# IOTBeev0_21.net
KiCad netlist of a schematic drawn in EAGLE
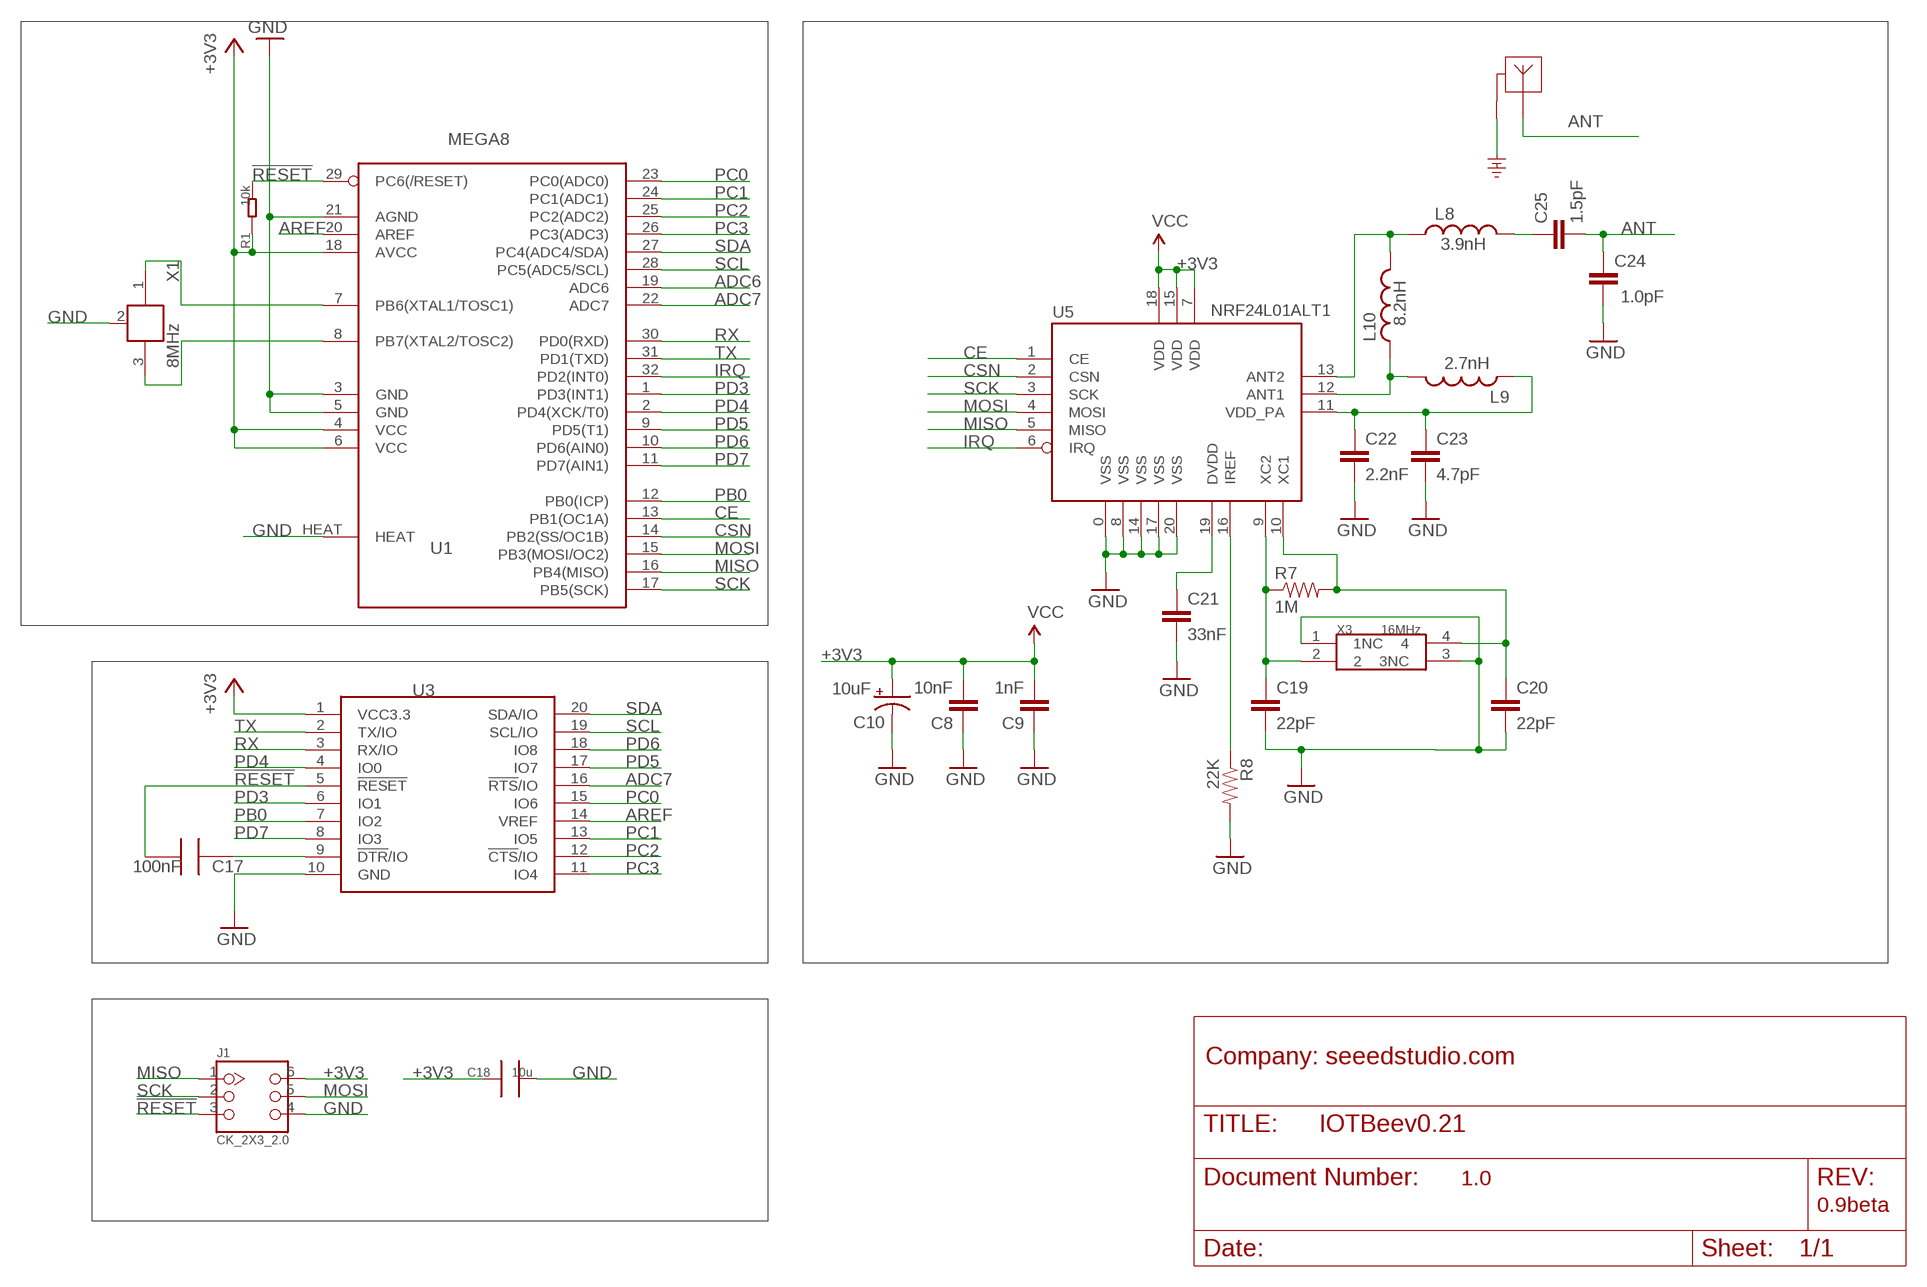
[diagram p0: schematic, sheet 1]

(export (version "E")
  (design (tool "Eeschema 10.0.6"))
  (components
    (comp (ref "ANT1")
      (value "2.4G-ANT")
      (footprint "eagle-import:2.4G-ANT")
      (libsource (lib "eagle-import") (part "2.4G-ANT"))
    )
    (comp (ref "C8")
      (value "10nF")
      (footprint "eagle-import:0402-CAP")
      (libsource (lib "eagle-import") (part "CAP0402-CAP"))
    )
    (comp (ref "C9")
      (value "1nF")
      (footprint "eagle-import:0402-CAP")
      (libsource (lib "eagle-import") (part "CAP0402-CAP"))
    )
    (comp (ref "C10")
      (value "10uF")
      (footprint "eagle-import:EIA3528")
      (libsource (lib "eagle-import") (part "CAP_POL3528"))
    )
    (comp (ref "C17")
      (value "100nF")
      (footprint "eagle-import:0603_S")
      (libsource (lib "eagle-import") (part "C0603_S"))
    )
    (comp (ref "C18")
      (value "10u")
      (footprint "eagle-import:0805")
      (libsource (lib "eagle-import") (part "C0805"))
    )
    (comp (ref "C19")
      (value "22pF")
      (footprint "eagle-import:0402-CAP")
      (libsource (lib "eagle-import") (part "CAP0402-CAP"))
    )
    (comp (ref "C20")
      (value "22pF")
      (footprint "eagle-import:0402-CAP")
      (libsource (lib "eagle-import") (part "CAP0402-CAP"))
    )
    (comp (ref "C21")
      (value "33nF")
      (footprint "eagle-import:0402-CAP")
      (libsource (lib "eagle-import") (part "CAP0402-CAP"))
    )
    (comp (ref "C22")
      (value "2.2nF")
      (footprint "eagle-import:0402-CAP")
      (libsource (lib "eagle-import") (part "CAP0402-CAP"))
    )
    (comp (ref "C23")
      (value "4.7pF")
      (footprint "eagle-import:0402-CAP")
      (libsource (lib "eagle-import") (part "CAP0402-CAP"))
    )
    (comp (ref "C24")
      (value "1.0pF")
      (footprint "eagle-import:0402-CAP")
      (libsource (lib "eagle-import") (part "CAP0402-CAP"))
    )
    (comp (ref "C25")
      (value "1.5pF")
      (footprint "eagle-import:0402-CAP")
      (libsource (lib "eagle-import") (part "CAP0402-CAP"))
    )
    (comp (ref "J1")
      (value "CK_2X3_2.0")
      (footprint "eagle-import:CK_2X3_2.0")
      (libsource (lib "eagle-import") (part "CK_2X3_2.0"))
    )
    (comp (ref "L8")
      (value "3.9nH")
      (footprint "eagle-import:C0402")
      (libsource (lib "eagle-import") (part "INDUCTOR0402"))
    )
    (comp (ref "L9")
      (value "2.7nH")
      (footprint "eagle-import:C0402")
      (libsource (lib "eagle-import") (part "INDUCTOR0402"))
    )
    (comp (ref "L10")
      (value "8.2nH")
      (footprint "eagle-import:C0402")
      (libsource (lib "eagle-import") (part "INDUCTOR0402"))
    )
    (comp (ref "R1")
      (value "10k")
      (footprint "eagle-import:0603_S")
      (libsource (lib "eagle-import") (part "R0603_S"))
    )
    (comp (ref "R7")
      (value "1M")
      (footprint "eagle-import:0402-RES")
      (libsource (lib "eagle-import") (part "RESISTOR0402-RES"))
    )
    (comp (ref "R8")
      (value "22K")
      (footprint "eagle-import:0402-RES")
      (libsource (lib "eagle-import") (part "RESISTOR0402-RES"))
    )
    (comp (ref "U1")
      (value "MEGA8")
      (footprint "eagle-import:MLF32X")
      (libsource (lib "eagle-import") (part "MEGA8"))
    )
    (comp (ref "U3")
      (value "BEE-OPENBEE-BTSMD")
      (footprint "eagle-import:20P-SMD-2.0-BT")
      (libsource (lib "eagle-import") (part "BEE-OPENBEE-BTSMD"))
    )
    (comp (ref "U5")
      (value "NRF24L01ALT1")
      (footprint "eagle-import:QFN20_ALT1")
      (libsource (lib "eagle-import") (part "NRF24L01ALT1"))
    )
    (comp (ref "X1")
      (value "8MHz")
      (footprint "eagle-import:XTAL_3X2")
      (libsource (lib "eagle-import") (part "XTAL_NCVER"))
    )
    (comp (ref "X3")
      (value "16MHz")
      (footprint "eagle-import:X3225")
      (libsource (lib "eagle-import") (part "XTAL_SMD_3225"))
    )
  )
  (nets
    (net (code "1") (name "+3V3") (class "Default")
      (node (ref "C10") (pin "A") (pinfunction "+_A") (pintype "passive"))
      (node (ref "C18") (pin "1") (pinfunction "1_1") (pintype "bidirectional"))
      (node (ref "C8") (pin "2") (pinfunction "2_2") (pintype "passive"))
      (node (ref "C9") (pin "2") (pinfunction "2_2") (pintype "passive"))
      (node (ref "J1") (pin "6") (pinfunction "P$6_6") (pintype "bidirectional"))
      (node (ref "R1") (pin "1") (pinfunction "1_1") (pintype "bidirectional"))
      (node (ref "U1") (pin "18") (pinfunction "AVCC_18") (pintype "bidirectional"))
      (node (ref "U1") (pin "4") (pinfunction "VCC_4") (pintype "bidirectional"))
      (node (ref "U1") (pin "6") (pinfunction "VCC_6") (pintype "bidirectional"))
      (node (ref "U3") (pin "1") (pinfunction "VCC3.3_1") (pintype "bidirectional"))
      (node (ref "U5") (pin "15") (pinfunction "VDD_15") (pintype "power_in"))
      (node (ref "U5") (pin "18") (pinfunction "VDD_18") (pintype "power_in"))
      (node (ref "U5") (pin "7") (pinfunction "VDD_7") (pintype "power_in"))
    )
    (net (code "2") (name "/ADC6") (class "Default")
      (node (ref "U1") (pin "19") (pinfunction "ADC6_19") (pintype "bidirectional"))
    )
    (net (code "3") (name "/ADC7") (class "Default")
      (node (ref "U1") (pin "22") (pinfunction "ADC7_22") (pintype "bidirectional"))
      (node (ref "U3") (pin "16") (pinfunction "~{RTS}/IO_16") (pintype "bidirectional"))
    )
    (net (code "4") (name "/ANT") (class "Default")
      (node (ref "ANT1") (pin "2") (pinfunction "2_2") (pintype "bidirectional"))
      (node (ref "C24") (pin "2") (pinfunction "2_2") (pintype "passive"))
      (node (ref "C25") (pin "2") (pinfunction "2_2") (pintype "passive"))
    )
    (net (code "5") (name "/AREF") (class "Default")
      (node (ref "U1") (pin "20") (pinfunction "AREF_20") (pintype "bidirectional"))
      (node (ref "U3") (pin "14") (pinfunction "VREF_14") (pintype "bidirectional"))
    )
    (net (code "6") (name "/CE") (class "Default")
      (node (ref "U1") (pin "13") (pinfunction "PB1(OC1A)_13") (pintype "bidirectional"))
      (node (ref "U5") (pin "1") (pinfunction "CE_1") (pintype "input"))
    )
    (net (code "7") (name "/CSN") (class "Default")
      (node (ref "U1") (pin "14") (pinfunction "PB2(SS/OC1B)_14") (pintype "bidirectional"))
      (node (ref "U5") (pin "2") (pinfunction "CSN_2") (pintype "input"))
    )
    (net (code "8") (name "/IRQ") (class "Default")
      (node (ref "U1") (pin "32") (pinfunction "PD2(INT0)_32") (pintype "bidirectional"))
      (node (ref "U5") (pin "6") (pinfunction "IRQ_6") (pintype "output"))
    )
    (net (code "9") (name "/MISO") (class "Default")
      (node (ref "J1") (pin "1") (pinfunction "P$1_1") (pintype "bidirectional"))
      (node (ref "U1") (pin "16") (pinfunction "PB4(MISO)_16") (pintype "bidirectional"))
      (node (ref "U5") (pin "5") (pinfunction "MISO_5") (pintype "output"))
    )
    (net (code "10") (name "/MOSI") (class "Default")
      (node (ref "J1") (pin "5") (pinfunction "P$5_5") (pintype "bidirectional"))
      (node (ref "U1") (pin "15") (pinfunction "PB3(MOSI/OC2)_15") (pintype "bidirectional"))
      (node (ref "U5") (pin "4") (pinfunction "MOSI_4") (pintype "input"))
    )
    (net (code "11") (name "/PB0") (class "Default")
      (node (ref "U1") (pin "12") (pinfunction "PB0(ICP)_12") (pintype "bidirectional"))
      (node (ref "U3") (pin "7") (pinfunction "IO2_7") (pintype "bidirectional"))
    )
    (net (code "12") (name "/PC0") (class "Default")
      (node (ref "U1") (pin "23") (pinfunction "PC0(ADC0)_23") (pintype "bidirectional"))
      (node (ref "U3") (pin "15") (pinfunction "IO6_15") (pintype "bidirectional"))
    )
    (net (code "13") (name "/PC1") (class "Default")
      (node (ref "U1") (pin "24") (pinfunction "PC1(ADC1)_24") (pintype "bidirectional"))
      (node (ref "U3") (pin "13") (pinfunction "IO5_13") (pintype "bidirectional"))
    )
    (net (code "14") (name "/PC2") (class "Default")
      (node (ref "U1") (pin "25") (pinfunction "PC2(ADC2)_25") (pintype "bidirectional"))
      (node (ref "U3") (pin "12") (pinfunction "~{CTS}/IO_12") (pintype "bidirectional"))
    )
    (net (code "15") (name "/PC3") (class "Default")
      (node (ref "U1") (pin "26") (pinfunction "PC3(ADC3)_26") (pintype "bidirectional"))
      (node (ref "U3") (pin "11") (pinfunction "IO4_11") (pintype "bidirectional"))
    )
    (net (code "16") (name "/PD3") (class "Default")
      (node (ref "U1") (pin "1") (pinfunction "PD3(INT1)_1") (pintype "bidirectional"))
      (node (ref "U3") (pin "6") (pinfunction "IO1_6") (pintype "bidirectional"))
    )
    (net (code "17") (name "/PD4") (class "Default")
      (node (ref "U1") (pin "2") (pinfunction "PD4(XCK/T0)_2") (pintype "bidirectional"))
      (node (ref "U3") (pin "4") (pinfunction "IO0_4") (pintype "bidirectional"))
    )
    (net (code "18") (name "/PD5") (class "Default")
      (node (ref "U1") (pin "9") (pinfunction "PD5(T1)_9") (pintype "bidirectional"))
      (node (ref "U3") (pin "17") (pinfunction "IO7_17") (pintype "bidirectional"))
    )
    (net (code "19") (name "/PD6") (class "Default")
      (node (ref "U1") (pin "10") (pinfunction "PD6(AIN0)_10") (pintype "bidirectional"))
      (node (ref "U3") (pin "18") (pinfunction "IO8_18") (pintype "bidirectional"))
    )
    (net (code "20") (name "/PD7") (class "Default")
      (node (ref "U1") (pin "11") (pinfunction "PD7(AIN1)_11") (pintype "bidirectional"))
      (node (ref "U3") (pin "8") (pinfunction "IO3_8") (pintype "bidirectional"))
    )
    (net (code "21") (name "/RX") (class "Default")
      (node (ref "U1") (pin "30") (pinfunction "PD0(RXD)_30") (pintype "bidirectional"))
      (node (ref "U3") (pin "3") (pinfunction "RX/IO_3") (pintype "bidirectional"))
    )
    (net (code "22") (name "/SCK") (class "Default")
      (node (ref "J1") (pin "2") (pinfunction "P$2_2") (pintype "bidirectional"))
      (node (ref "U1") (pin "17") (pinfunction "PB5(SCK)_17") (pintype "bidirectional"))
      (node (ref "U5") (pin "3") (pinfunction "SCK_3") (pintype "input"))
    )
    (net (code "23") (name "/SCL") (class "Default")
      (node (ref "U1") (pin "28") (pinfunction "PC5(ADC5/SCL)_28") (pintype "bidirectional"))
      (node (ref "U3") (pin "19") (pinfunction "SCL/IO_19") (pintype "bidirectional"))
    )
    (net (code "24") (name "/SDA") (class "Default")
      (node (ref "U1") (pin "27") (pinfunction "PC4(ADC4/SDA)_27") (pintype "bidirectional"))
      (node (ref "U3") (pin "20") (pinfunction "SDA/IO_20") (pintype "bidirectional"))
    )
    (net (code "25") (name "/TX") (class "Default")
      (node (ref "U1") (pin "31") (pinfunction "PD1(TXD)_31") (pintype "bidirectional"))
      (node (ref "U3") (pin "2") (pinfunction "TX/IO_2") (pintype "bidirectional"))
    )
    (net (code "26") (name "/~{RESET}") (class "Default")
      (node (ref "C17") (pin "2") (pinfunction "2_2") (pintype "bidirectional"))
      (node (ref "J1") (pin "3") (pinfunction "P$3_3") (pintype "bidirectional"))
      (node (ref "R1") (pin "2") (pinfunction "2_2") (pintype "bidirectional"))
      (node (ref "U1") (pin "29") (pinfunction "PC6(/RESET)_29") (pintype "bidirectional"))
      (node (ref "U3") (pin "5") (pinfunction "~{RESET}_5") (pintype "bidirectional"))
    )
    (net (code "27") (name "GND") (class "Default")
      (node (ref "ANT1") (pin "1") (pinfunction "1_1") (pintype "bidirectional"))
      (node (ref "C10") (pin "C") (pinfunction "-_C") (pintype "passive"))
      (node (ref "C18") (pin "2") (pinfunction "2_2") (pintype "bidirectional"))
      (node (ref "C19") (pin "2") (pinfunction "2_2") (pintype "passive"))
      (node (ref "C20") (pin "2") (pinfunction "2_2") (pintype "passive"))
      (node (ref "C21") (pin "2") (pinfunction "2_2") (pintype "passive"))
      (node (ref "C22") (pin "2") (pinfunction "2_2") (pintype "passive"))
      (node (ref "C23") (pin "2") (pinfunction "2_2") (pintype "passive"))
      (node (ref "C24") (pin "1") (pinfunction "1_1") (pintype "passive"))
      (node (ref "C8") (pin "1") (pinfunction "1_1") (pintype "passive"))
      (node (ref "C9") (pin "1") (pinfunction "1_1") (pintype "passive"))
      (node (ref "J1") (pin "4") (pinfunction "P$4_4") (pintype "bidirectional"))
      (node (ref "R8") (pin "2") (pinfunction "2_2") (pintype "passive"))
      (node (ref "U1") (pin "21") (pinfunction "AGND_21") (pintype "bidirectional"))
      (node (ref "U1") (pin "3") (pinfunction "GND_3") (pintype "bidirectional"))
      (node (ref "U1") (pin "5") (pinfunction "GND_5") (pintype "bidirectional"))
      (node (ref "U1") (pin "HEAT") (pinfunction "HEAT_HEAT") (pintype "bidirectional"))
      (node (ref "U3") (pin "10") (pinfunction "GND_10") (pintype "bidirectional"))
      (node (ref "U5") (pin "0") (pinfunction "VSS_0") (pintype "power_in"))
      (node (ref "U5") (pin "14") (pinfunction "VSS_14") (pintype "power_in"))
      (node (ref "U5") (pin "17") (pinfunction "VSS_17") (pintype "power_in"))
      (node (ref "U5") (pin "20") (pinfunction "VSS_20") (pintype "power_in"))
      (node (ref "U5") (pin "8") (pinfunction "VSS_8") (pintype "power_in"))
      (node (ref "X1") (pin "2") (pinfunction "GND_2") (pintype "bidirectional"))
      (node (ref "X3") (pin "1") (pinfunction "1NC_1") (pintype "bidirectional"))
      (node (ref "X3") (pin "3") (pinfunction "3NC_3") (pintype "bidirectional"))
    )
    (net (code "28") (name "Net-(C25-Pad1)") (class "Default")
      (node (ref "C25") (pin "1") (pinfunction "1_1") (pintype "passive"))
      (node (ref "L8") (pin "2") (pinfunction "2_2") (pintype "passive"))
    )
    (net (code "29") (name "Net-(U1-PB6(XTAL1{slash}TOSC1))") (class "Default")
      (node (ref "U1") (pin "7") (pinfunction "PB6(XTAL1/TOSC1)_7") (pintype "bidirectional"))
      (node (ref "X1") (pin "1") (pinfunction "1_1") (pintype "bidirectional"))
    )
    (net (code "30") (name "Net-(U1-PB7(XTAL2{slash}TOSC2))") (class "Default")
      (node (ref "U1") (pin "8") (pinfunction "PB7(XTAL2/TOSC2)_8") (pintype "bidirectional"))
      (node (ref "X1") (pin "3") (pinfunction "2_3") (pintype "bidirectional"))
    )
    (net (code "31") (name "Net-(U3-~{DTR}{slash}IO)") (class "Default")
      (node (ref "C17") (pin "1") (pinfunction "1_1") (pintype "bidirectional"))
      (node (ref "U3") (pin "9") (pinfunction "~{DTR}/IO_9") (pintype "bidirectional"))
    )
    (net (code "32") (name "Net-(U5-ANT1)") (class "Default")
      (node (ref "L10") (pin "1") (pinfunction "1_1") (pintype "passive"))
      (node (ref "L9") (pin "2") (pinfunction "2_2") (pintype "passive"))
      (node (ref "U5") (pin "12") (pinfunction "ANT1_12") (pintype "output"))
    )
    (net (code "33") (name "Net-(U5-ANT2)") (class "Default")
      (node (ref "L10") (pin "2") (pinfunction "2_2") (pintype "passive"))
      (node (ref "L8") (pin "1") (pinfunction "1_1") (pintype "passive"))
      (node (ref "U5") (pin "13") (pinfunction "ANT2_13") (pintype "output"))
    )
    (net (code "34") (name "Net-(U5-DVDD)") (class "Default")
      (node (ref "C21") (pin "1") (pinfunction "1_1") (pintype "passive"))
      (node (ref "U5") (pin "19") (pinfunction "DVDD_19") (pintype "power_in"))
    )
    (net (code "35") (name "Net-(U5-IREF)") (class "Default")
      (node (ref "R8") (pin "1") (pinfunction "1_1") (pintype "passive"))
      (node (ref "U5") (pin "16") (pinfunction "IREF_16") (pintype "input"))
    )
    (net (code "36") (name "Net-(U5-VDD_PA)") (class "Default")
      (node (ref "C22") (pin "1") (pinfunction "1_1") (pintype "passive"))
      (node (ref "C23") (pin "1") (pinfunction "1_1") (pintype "passive"))
      (node (ref "L9") (pin "1") (pinfunction "1_1") (pintype "passive"))
      (node (ref "U5") (pin "11") (pinfunction "VDD_PA_11") (pintype "power_in"))
    )
    (net (code "37") (name "Net-(U5-XC1)") (class "Default")
      (node (ref "C20") (pin "1") (pinfunction "1_1") (pintype "passive"))
      (node (ref "R7") (pin "2") (pinfunction "2_2") (pintype "passive"))
      (node (ref "U5") (pin "10") (pinfunction "XC1_10") (pintype "input"))
      (node (ref "X3") (pin "4") (pinfunction "4_4") (pintype "bidirectional"))
    )
    (net (code "38") (name "Net-(U5-XC2)") (class "Default")
      (node (ref "C19") (pin "1") (pinfunction "1_1") (pintype "passive"))
      (node (ref "R7") (pin "1") (pinfunction "1_1") (pintype "passive"))
      (node (ref "U5") (pin "9") (pinfunction "XC2_9") (pintype "input"))
      (node (ref "X3") (pin "2") (pinfunction "2_2") (pintype "bidirectional"))
    )
  )
)
